# HAT.net
KiCad netlist of a schematic drawn in Altium Designer
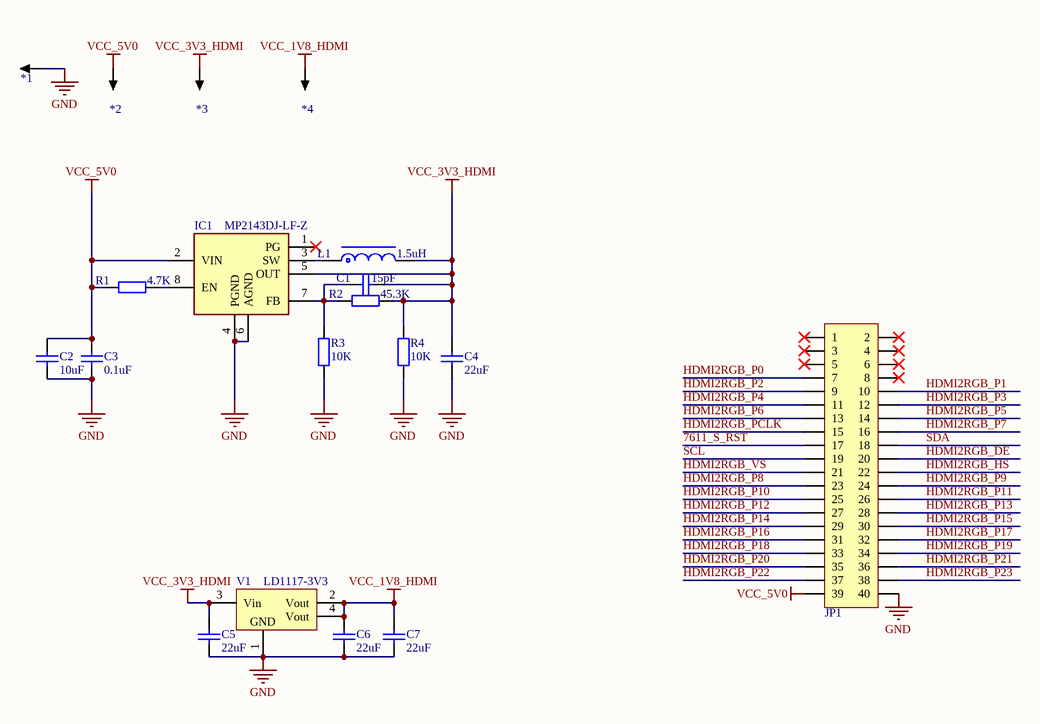
[diagram p0: HAT.SchDoc]

(export (version "E")
  (design (tool "Eeschema 10.0.6"))
  (components
    (comp (ref "*1")
      (value "CS")
      (footprint "R100")
      (description "探针焊盘")
      (libsource (lib "0.7 - 常用按键-开关-蜂鸣器-电池-测试点") (part "CS"))
    )
    (comp (ref "*2")
      (value "CS")
      (footprint "R100")
      (description "探针焊盘")
      (libsource (lib "0.7 - 常用按键-开关-蜂鸣器-电池-测试点") (part "CS"))
    )
    (comp (ref "*3")
      (value "CS")
      (footprint "R100")
      (description "探针焊盘")
      (libsource (lib "0.7 - 常用按键-开关-蜂鸣器-电池-测试点") (part "CS"))
    )
    (comp (ref "*4")
      (value "CS")
      (footprint "R100")
      (description "探针焊盘")
      (libsource (lib "0.7 - 常用按键-开关-蜂鸣器-电池-测试点") (part "CS"))
    )
    (comp (ref "C1")
      (value "15pF")
      (footprint "C0402_L")
      (description "贴片电容")
      (libsource (lib "0.1 - 电阻-电容-电感-磁珠-电位器") (part "C"))
    )
    (comp (ref "C2")
      (value "10uF")
      (footprint "C0805_L")
      (description "贴片电容")
      (libsource (lib "0.1 - 电阻-电容-电感-磁珠-电位器") (part "C"))
    )
    (comp (ref "C3")
      (value "0.1uF")
      (footprint "C0402_L")
      (description "贴片电容")
      (libsource (lib "0.1 - 电阻-电容-电感-磁珠-电位器") (part "C"))
    )
    (comp (ref "C4")
      (value "22uF")
      (footprint "C0805_L")
      (description "贴片电容")
      (libsource (lib "0.1 - 电阻-电容-电感-磁珠-电位器") (part "C"))
    )
    (comp (ref "C5")
      (value "22uF")
      (footprint "C0603_L")
      (description "贴片电容")
      (libsource (lib "0.1 - 电阻-电容-电感-磁珠-电位器") (part "C"))
    )
    (comp (ref "C6")
      (value "22uF")
      (footprint "C0603_L")
      (description "贴片电容")
      (libsource (lib "0.1 - 电阻-电容-电感-磁珠-电位器") (part "C"))
    )
    (comp (ref "C7")
      (value "22uF")
      (footprint "C0805_L")
      (description "贴片电容")
      (libsource (lib "0.1 - 电阻-电容-电感-磁珠-电位器") (part "C"))
    )
    (comp (ref "IC1")
      (value "MP2143DJ-LF-Z")
      (footprint "SamacSys:SOP65P280X100-8N")
      (description "Integrated Circuit")
      (fields (field (name "MOUSER PART NUMBER") "946-MP2143DJLFZ"))
      (libsource (lib "SamacSys") (part "MP2143DJ-LF-Z"))
    )
    (comp (ref "JP1")
      (value "Header 2X11")
      (footprint "PHD2.0-LI-2x20P")
      (description "20*2P接插件")
      (libsource (lib "5.4 - 接插件-脚距2.0") (part "Header 20X2"))
    )
    (comp (ref "L1")
      (value "1.5uH")
      (footprint "NR3010")
      (description "太诱-NR磁胶电感")
      (fields (field (name "4.作者声明") "旨为整合最全库集,欢迎转载,禁止商用！-冰凌猫") (field (name "1.库作者") "冰凌猫"))
      (libsource (lib "0.1 - 电阻-电容-电感-磁珠-电位器") (part "L-NR"))
    )
    (comp (ref "R1")
      (value "4.7K")
      (footprint "R0402_L")
      (description "贴片电阻")
      (libsource (lib "0.1 - 电阻-电容-电感-磁珠-电位器") (part "R"))
    )
    (comp (ref "R2")
      (value "45.3K")
      (footprint "R0402_L")
      (description "贴片电阻")
      (libsource (lib "0.1 - 电阻-电容-电感-磁珠-电位器") (part "R"))
    )
    (comp (ref "R3")
      (value "10K")
      (footprint "R0402_L")
      (description "贴片电阻")
      (libsource (lib "0.1 - 电阻-电容-电感-磁珠-电位器") (part "R"))
    )
    (comp (ref "R4")
      (value "10K")
      (footprint "R0402_L")
      (description "贴片电阻")
      (libsource (lib "0.1 - 电阻-电容-电感-磁珠-电位器") (part "R"))
    )
    (comp (ref "V1")
      (value "LD1117-3V3")
      (footprint "SOT223_L")
      (description "三端稳压芯片")
      (libsource (lib "1.1 - 电源类芯片") (part "LD1117"))
    )
  )
  (nets
    (net (code "1") (name "/7611_S_RST") (class "Default")
      (node (ref "JP1") (pin "17") (pinfunction "17_17") (pintype "passive"))
    )
    (net (code "2") (name "/HDMI2RGB_DE") (class "Default")
      (node (ref "JP1") (pin "20") (pinfunction "20_20") (pintype "passive"))
    )
    (net (code "3") (name "/HDMI2RGB_HS") (class "Default")
      (node (ref "JP1") (pin "22") (pinfunction "22_22") (pintype "passive"))
    )
    (net (code "4") (name "/HDMI2RGB_P0") (class "Default")
      (node (ref "JP1") (pin "7") (pinfunction "7_7") (pintype "passive"))
    )
    (net (code "5") (name "/HDMI2RGB_P1") (class "Default")
      (node (ref "JP1") (pin "10") (pinfunction "10_10") (pintype "passive"))
    )
    (net (code "6") (name "/HDMI2RGB_P2") (class "Default")
      (node (ref "JP1") (pin "9") (pinfunction "9_9") (pintype "passive"))
    )
    (net (code "7") (name "/HDMI2RGB_P3") (class "Default")
      (node (ref "JP1") (pin "12") (pinfunction "12_12") (pintype "passive"))
    )
    (net (code "8") (name "/HDMI2RGB_P4") (class "Default")
      (node (ref "JP1") (pin "11") (pinfunction "11_11") (pintype "passive"))
    )
    (net (code "9") (name "/HDMI2RGB_P5") (class "Default")
      (node (ref "JP1") (pin "14") (pinfunction "14_14") (pintype "passive"))
    )
    (net (code "10") (name "/HDMI2RGB_P6") (class "Default")
      (node (ref "JP1") (pin "13") (pinfunction "13_13") (pintype "passive"))
    )
    (net (code "11") (name "/HDMI2RGB_P7") (class "Default")
      (node (ref "JP1") (pin "16") (pinfunction "16_16") (pintype "passive"))
    )
    (net (code "12") (name "/HDMI2RGB_P8") (class "Default")
      (node (ref "JP1") (pin "23") (pinfunction "23_23") (pintype "passive"))
    )
    (net (code "13") (name "/HDMI2RGB_P9") (class "Default")
      (node (ref "JP1") (pin "24") (pinfunction "24_24") (pintype "passive"))
    )
    (net (code "14") (name "/HDMI2RGB_P10") (class "Default")
      (node (ref "JP1") (pin "25") (pinfunction "25_25") (pintype "passive"))
    )
    (net (code "15") (name "/HDMI2RGB_P11") (class "Default")
      (node (ref "JP1") (pin "26") (pinfunction "26_26") (pintype "passive"))
    )
    (net (code "16") (name "/HDMI2RGB_P12") (class "Default")
      (node (ref "JP1") (pin "27") (pinfunction "27_27") (pintype "passive"))
    )
    (net (code "17") (name "/HDMI2RGB_P13") (class "Default")
      (node (ref "JP1") (pin "28") (pinfunction "28_28") (pintype "passive"))
    )
    (net (code "18") (name "/HDMI2RGB_P14") (class "Default")
      (node (ref "JP1") (pin "29") (pinfunction "29_29") (pintype "passive"))
    )
    (net (code "19") (name "/HDMI2RGB_P15") (class "Default")
      (node (ref "JP1") (pin "30") (pinfunction "30_30") (pintype "passive"))
    )
    (net (code "20") (name "/HDMI2RGB_P16") (class "Default")
      (node (ref "JP1") (pin "31") (pinfunction "31_31") (pintype "passive"))
    )
    (net (code "21") (name "/HDMI2RGB_P17") (class "Default")
      (node (ref "JP1") (pin "32") (pinfunction "32_32") (pintype "passive"))
    )
    (net (code "22") (name "/HDMI2RGB_P18") (class "Default")
      (node (ref "JP1") (pin "33") (pinfunction "33_33") (pintype "passive"))
    )
    (net (code "23") (name "/HDMI2RGB_P19") (class "Default")
      (node (ref "JP1") (pin "34") (pinfunction "34_34") (pintype "passive"))
    )
    (net (code "24") (name "/HDMI2RGB_P20") (class "Default")
      (node (ref "JP1") (pin "35") (pinfunction "35_35") (pintype "passive"))
    )
    (net (code "25") (name "/HDMI2RGB_P21") (class "Default")
      (node (ref "JP1") (pin "36") (pinfunction "36_36") (pintype "passive"))
    )
    (net (code "26") (name "/HDMI2RGB_P22") (class "Default")
      (node (ref "JP1") (pin "37") (pinfunction "37_37") (pintype "passive"))
    )
    (net (code "27") (name "/HDMI2RGB_P23") (class "Default")
      (node (ref "JP1") (pin "38") (pinfunction "38_38") (pintype "passive"))
    )
    (net (code "28") (name "/HDMI2RGB_PCLK") (class "Default")
      (node (ref "JP1") (pin "15") (pinfunction "15_15") (pintype "passive"))
    )
    (net (code "29") (name "/HDMI2RGB_VS") (class "Default")
      (node (ref "JP1") (pin "21") (pinfunction "21_21") (pintype "passive"))
    )
    (net (code "30") (name "/SCL") (class "Default")
      (node (ref "JP1") (pin "19") (pinfunction "19_19") (pintype "passive"))
    )
    (net (code "31") (name "/SDA") (class "Default")
      (node (ref "JP1") (pin "18") (pinfunction "18_18") (pintype "passive"))
    )
    (net (code "32") (name "GND") (class "Default")
      (node (ref "*1") (pin "1") (pinfunction "1_1") (pintype "passive"))
      (node (ref "C2") (pin "1") (pinfunction "1_1") (pintype "passive"))
      (node (ref "C3") (pin "1") (pinfunction "1_1") (pintype "passive"))
      (node (ref "C4") (pin "1") (pinfunction "1_1") (pintype "passive"))
      (node (ref "C5") (pin "1") (pinfunction "1_1") (pintype "passive"))
      (node (ref "C6") (pin "1") (pinfunction "1_1") (pintype "passive"))
      (node (ref "C7") (pin "1") (pinfunction "1_1") (pintype "passive"))
      (node (ref "IC1") (pin "4") (pinfunction "PGND_4") (pintype "passive"))
      (node (ref "IC1") (pin "6") (pinfunction "AGND_6") (pintype "passive"))
      (node (ref "JP1") (pin "40") (pinfunction "40_40") (pintype "passive"))
      (node (ref "R3") (pin "1") (pinfunction "1_1") (pintype "passive"))
      (node (ref "R4") (pin "1") (pinfunction "1_1") (pintype "passive"))
      (node (ref "V1") (pin "1") (pinfunction "GND_1") (pintype "passive"))
    )
    (net (code "33") (name "Net-(IC1-EN)") (class "Default")
      (node (ref "IC1") (pin "8") (pinfunction "EN_8") (pintype "passive"))
      (node (ref "R1") (pin "1") (pinfunction "1_1") (pintype "passive"))
    )
    (net (code "34") (name "Net-(IC1-FB)") (class "Default")
      (node (ref "C1") (pin "2") (pinfunction "2_2") (pintype "passive"))
      (node (ref "IC1") (pin "7") (pinfunction "FB_7") (pintype "passive"))
      (node (ref "R2") (pin "2") (pinfunction "2_2") (pintype "passive"))
      (node (ref "R3") (pin "2") (pinfunction "2_2") (pintype "passive"))
    )
    (net (code "35") (name "Net-(IC1-SW)") (class "Default")
      (node (ref "IC1") (pin "3") (pinfunction "SW_3") (pintype "passive"))
      (node (ref "L1") (pin "1") (pinfunction "1_1") (pintype "passive"))
    )
    (net (code "36") (name "VCC_1V8_HDMI") (class "Default")
      (node (ref "*4") (pin "1") (pinfunction "1_1") (pintype "passive"))
      (node (ref "C6") (pin "2") (pinfunction "2_2") (pintype "passive"))
      (node (ref "C7") (pin "2") (pinfunction "2_2") (pintype "passive"))
      (node (ref "V1") (pin "2") (pinfunction "Vout_2") (pintype "passive"))
      (node (ref "V1") (pin "4") (pinfunction "Vout_4") (pintype "passive"))
    )
    (net (code "37") (name "VCC_3V3_HDMI") (class "Default")
      (node (ref "*3") (pin "1") (pinfunction "1_1") (pintype "passive"))
      (node (ref "C1") (pin "1") (pinfunction "1_1") (pintype "passive"))
      (node (ref "C4") (pin "2") (pinfunction "2_2") (pintype "passive"))
      (node (ref "C5") (pin "2") (pinfunction "2_2") (pintype "passive"))
      (node (ref "IC1") (pin "5") (pinfunction "OUT_5") (pintype "passive"))
      (node (ref "L1") (pin "2") (pinfunction "2_2") (pintype "passive"))
      (node (ref "R2") (pin "1") (pinfunction "1_1") (pintype "passive"))
      (node (ref "R4") (pin "2") (pinfunction "2_2") (pintype "passive"))
      (node (ref "V1") (pin "3") (pinfunction "Vin_3") (pintype "passive"))
    )
    (net (code "38") (name "VCC_5V0") (class "Default")
      (node (ref "*2") (pin "1") (pinfunction "1_1") (pintype "passive"))
      (node (ref "C2") (pin "2") (pinfunction "2_2") (pintype "passive"))
      (node (ref "C3") (pin "2") (pinfunction "2_2") (pintype "passive"))
      (node (ref "IC1") (pin "2") (pinfunction "VIN_2") (pintype "passive"))
      (node (ref "JP1") (pin "39") (pinfunction "39_39") (pintype "passive"))
      (node (ref "R1") (pin "2") (pinfunction "2_2") (pintype "passive"))
    )
    (net (code "39") (name "unconnected-(IC1-PG-Pad1)") (class "Default")
      (node (ref "IC1") (pin "1") (pinfunction "PG_1") (pintype "passive+no_connect"))
    )
    (net (code "40") (name "unconnected-(JP1-Pad1)") (class "Default")
      (node (ref "JP1") (pin "1") (pinfunction "1_1") (pintype "passive+no_connect"))
    )
    (net (code "41") (name "unconnected-(JP1-Pad2)") (class "Default")
      (node (ref "JP1") (pin "2") (pinfunction "2_2") (pintype "passive+no_connect"))
    )
    (net (code "42") (name "unconnected-(JP1-Pad3)") (class "Default")
      (node (ref "JP1") (pin "3") (pinfunction "3_3") (pintype "passive+no_connect"))
    )
    (net (code "43") (name "unconnected-(JP1-Pad4)") (class "Default")
      (node (ref "JP1") (pin "4") (pinfunction "4_4") (pintype "passive+no_connect"))
    )
    (net (code "44") (name "unconnected-(JP1-Pad5)") (class "Default")
      (node (ref "JP1") (pin "5") (pinfunction "5_5") (pintype "passive+no_connect"))
    )
    (net (code "45") (name "unconnected-(JP1-Pad6)") (class "Default")
      (node (ref "JP1") (pin "6") (pinfunction "6_6") (pintype "passive+no_connect"))
    )
    (net (code "46") (name "unconnected-(JP1-Pad8)") (class "Default")
      (node (ref "JP1") (pin "8") (pinfunction "8_8") (pintype "passive+no_connect"))
    )
  )
)
